# Power.net
KiCad netlist of a schematic drawn in Altium Designer
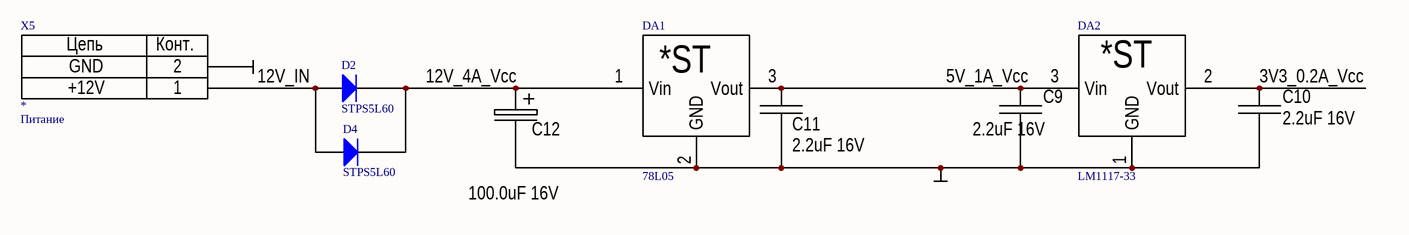
[diagram p0: Power.SchDoc]

(export (version "E")
  (design (tool "Eeschema 10.0.6"))
  (components
    (comp (ref "C9")
      (value "2.2uF 16V")
      (footprint "0805_CAP")
      (libsource (lib "Integrated_Library_tikhovikt") (part "Cap_np"))
    )
    (comp (ref "C10")
      (value "2.2uF 16V")
      (footprint "0805_CAP")
      (libsource (lib "Integrated_Library_tikhovikt") (part "Cap_np"))
    )
    (comp (ref "C11")
      (value "2.2uF 16V")
      (footprint "0805_CAP")
      (libsource (lib "Integrated_Library_tikhovikt") (part "Cap_np"))
    )
    (comp (ref "C12")
      (value "100.0uF 16V")
      (footprint "CAP_P_8mm_3.5mm")
      (libsource (lib "Integrated_Library_tikhovikt") (part "Cap_p"))
    )
    (comp (ref "D2")
      (value "STPS5L60")
      (footprint "SMC")
      (description "Default Diode")
      (fields (field (name "PUBLISHER") "Altium Limited"))
      (libsource (lib "Miscellaneous Devices") (part "Diode"))
    )
    (comp (ref "D4")
      (value "STPS5L60")
      (footprint "SMC")
      (description "Default Diode")
      (fields (field (name "PUBLISHER") "Altium Limited"))
      (libsource (lib "Miscellaneous Devices") (part "Diode"))
    )
    (comp (ref "DA1")
      (value "78L05")
      (footprint "to-220ab")
      (libsource (lib "Integrated_Library_tikhovikt") (part "78L05"))
    )
    (comp (ref "DA2")
      (value "LM1117-33")
      (footprint "dpack")
      (libsource (lib "Integrated_Library_tikhovikt") (part "LM1117"))
    )
    (comp (ref "X5")
      (value "*")
      (footprint "2pin_5.08")
      (fields (field (name "DESTINY") "Питание"))
      (libsource (lib "Integrated_Library_tikhovikt") (part "2pin_conn"))
    )
  )
  (nets
    (net (code "1") (name "/3V3_0.2A_Vcc") (class "Default")
      (node (ref "C10") (pin "2") (pinfunction "2_2") (pintype "passive"))
      (node (ref "DA2") (pin "2") (pinfunction "Vout_2") (pintype "passive"))
    )
    (net (code "2") (name "/5V_1A_Vcc") (class "Default")
      (node (ref "C11") (pin "2") (pinfunction "2_2") (pintype "passive"))
      (node (ref "C9") (pin "2") (pinfunction "2_2") (pintype "passive"))
      (node (ref "DA1") (pin "3") (pinfunction "Vout_3") (pintype "passive"))
      (node (ref "DA2") (pin "3") (pinfunction "Vin_3") (pintype "passive"))
    )
    (net (code "3") (name "/12V_4A_Vcc") (class "Default")
      (node (ref "C12") (pin "1") (pinfunction "1_1") (pintype "passive"))
      (node (ref "D2") (pin "2") (pinfunction "K_2") (pintype "passive"))
      (node (ref "D4") (pin "2") (pinfunction "K_2") (pintype "passive"))
      (node (ref "DA1") (pin "1") (pinfunction "Vin_1") (pintype "passive"))
    )
    (net (code "4") (name "/12V_IN") (class "Default")
      (node (ref "D2") (pin "1") (pinfunction "A_1") (pintype "passive"))
      (node (ref "D4") (pin "1") (pinfunction "A_1") (pintype "passive"))
      (node (ref "X5") (pin "1") (pinfunction "1_1") (pintype "passive"))
    )
    (net (code "5") (name "GND") (class "Default")
      (node (ref "C10") (pin "1") (pinfunction "1_1") (pintype "passive"))
      (node (ref "C11") (pin "1") (pinfunction "1_1") (pintype "passive"))
      (node (ref "C12") (pin "2") (pinfunction "2_2") (pintype "passive"))
      (node (ref "C9") (pin "1") (pinfunction "1_1") (pintype "passive"))
      (node (ref "DA1") (pin "2") (pinfunction "GND_2") (pintype "passive"))
      (node (ref "DA2") (pin "1") (pinfunction "GND_1") (pintype "passive"))
      (node (ref "X5") (pin "2") (pinfunction "2_2") (pintype "passive"))
    )
  )
)
